# LPEDT_revA1_bikeit_MCU_IO.net
KiCad netlist of a schematic drawn in Altium Designer
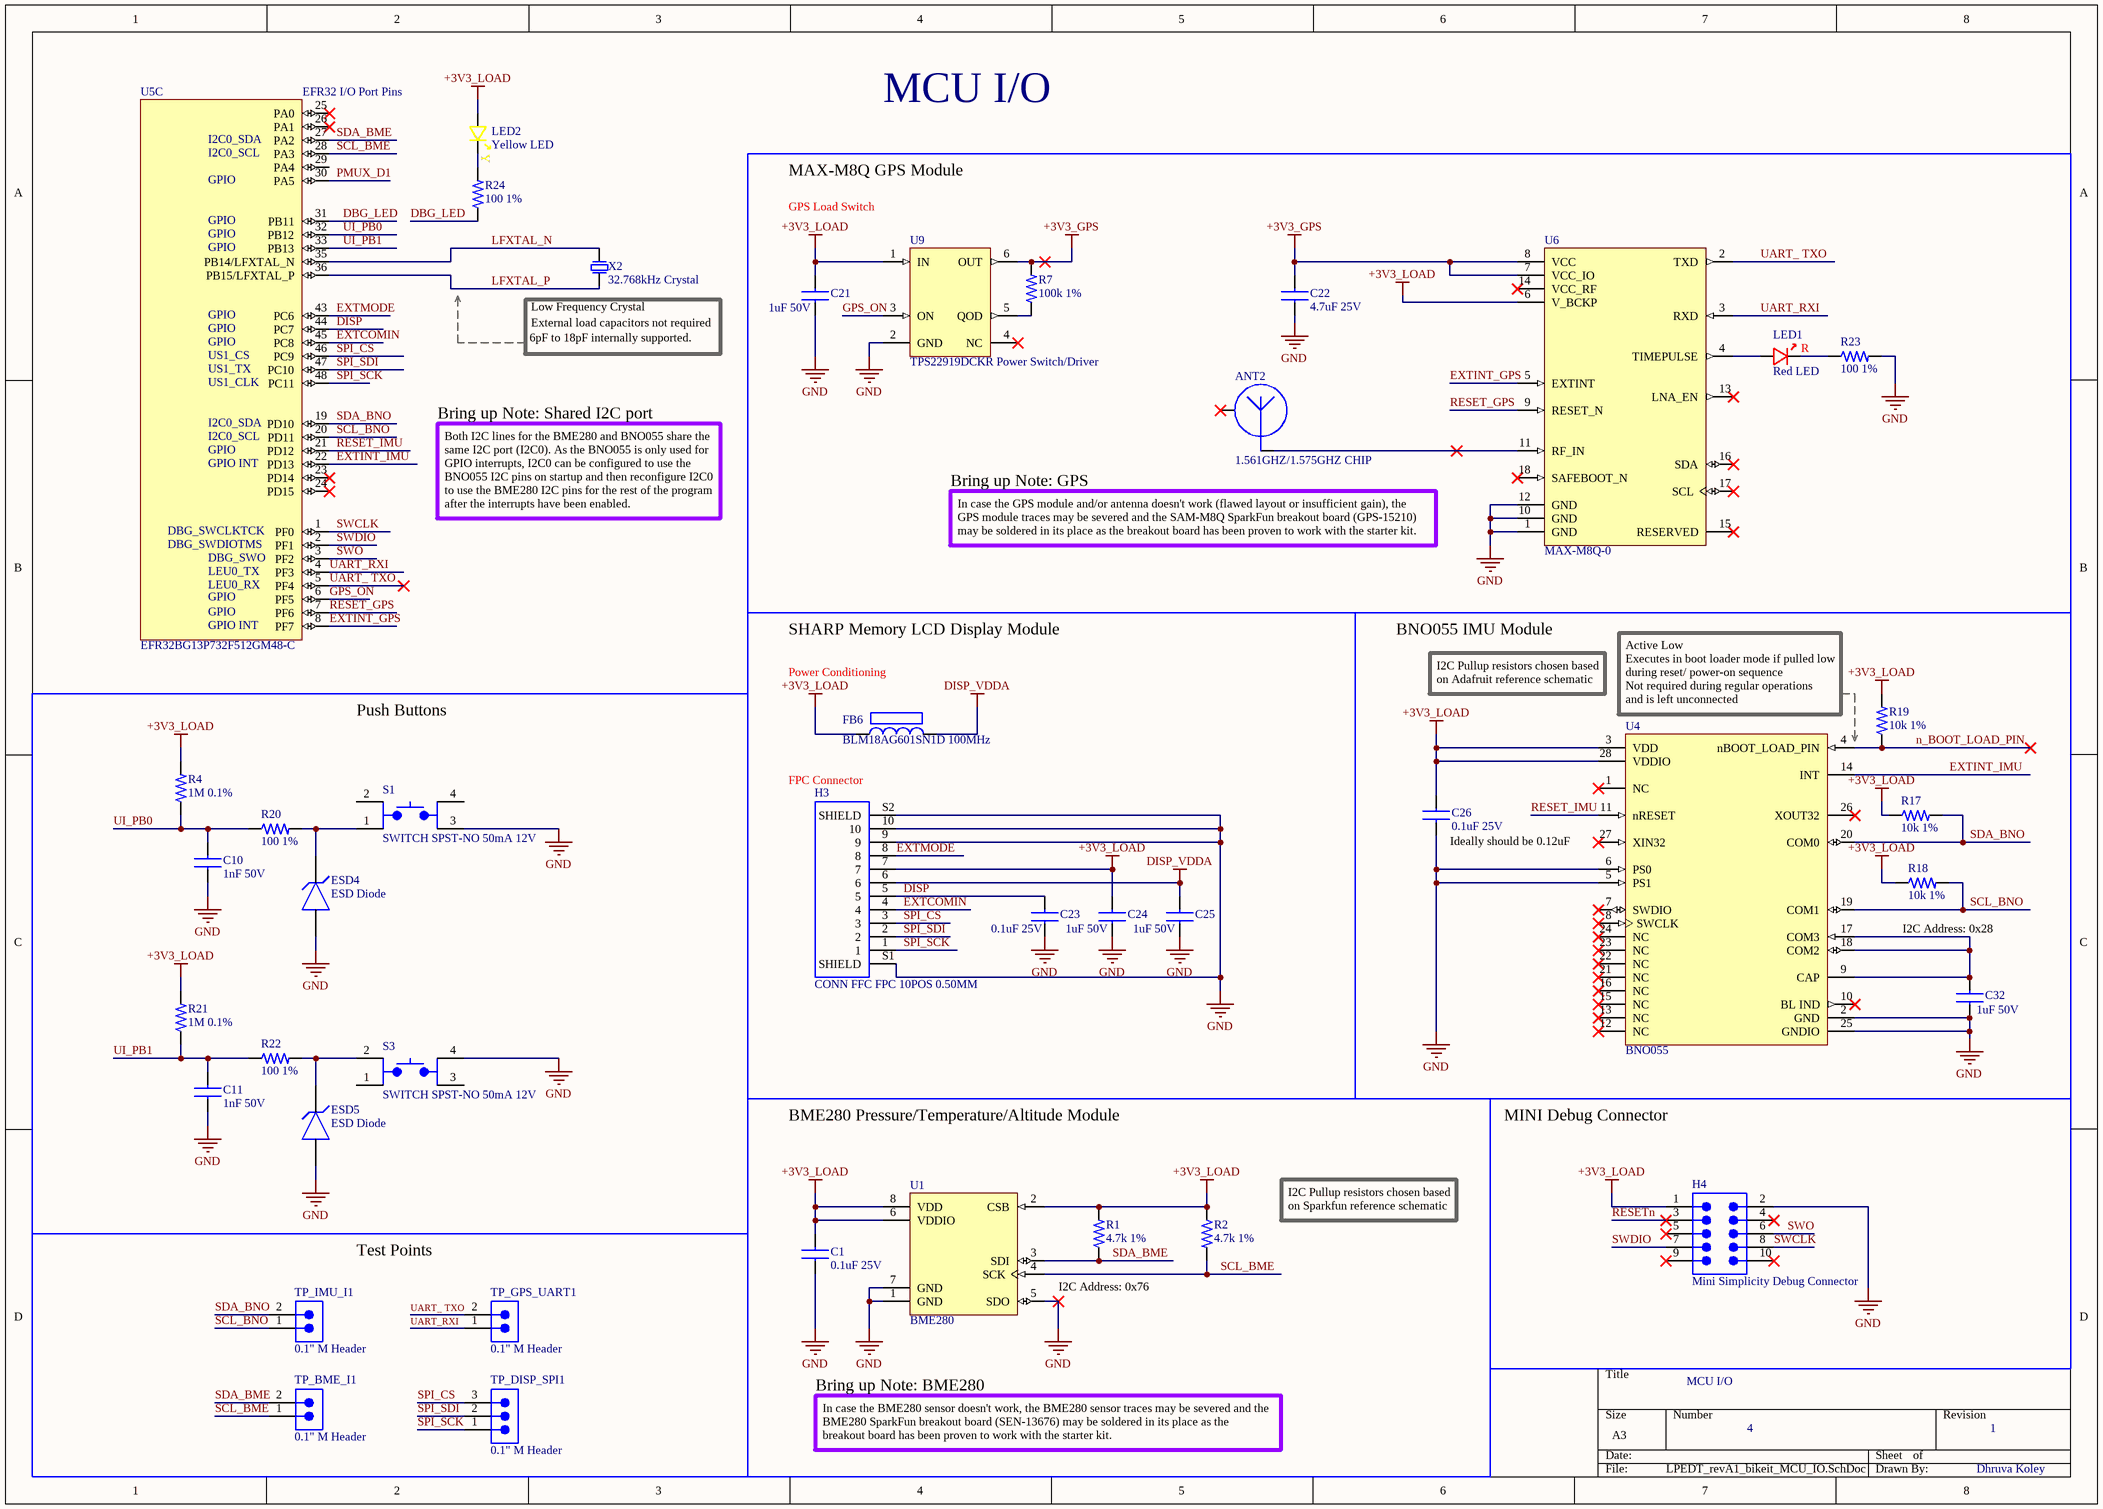
[diagram p0: LPEDT_revA1_bikeit_MCU_IO.SchDoc]

(export (version "E")
  (design (tool "Eeschema 10.0.6"))
  (components
    (comp (ref "ANT2")
      (value "1.561GHZ/1.575GHZ CHIP")
      (footprint "CHIP_ANTENNA")
      (description "RF ANT 1.561GHZ/1.575GHZ CHIP")
      (fields
        (field (name "MANUFACTURER") "Johanson")
        (field (name "MANUFACTURER PART NUMBER") "1575AT43A0040E")
      )
      (libsource (lib "LPEDT_revA1_bikeit_IL") (part "1575AT43A0040E"))
    )
    (comp (ref "C1")
      (value "0.1uF 25V")
      (footprint "CAP_0603_1.60mm*0.80mm")
      (description "CAP CER 0.1UF 25V X7R 0603")
      (fields
        (field (name "MANUFACTURER") "Murata")
        (field (name "MANUFACTURER PART NUMBER") "GCJ188R71E104KA12D")
      )
      (libsource (lib "LPEDT_revA1_bikeit") (part "GCJ188R71E104KA12D"))
    )
    (comp (ref "C10")
      (value "1nF 50V")
      (footprint "CAP_0603_1.60mm*0.80mm")
      (description "Cap Ceramic 0.001uF 50V X7R 10% Pad SMD 0603 125°C T/R")
      (fields
        (field (name "MANUFACTURER") "Samsung")
        (field (name "MANUFACTURER PART NUMBER") "CL10B102KB8NNNC")
      )
      (libsource (lib "LPEDT_revA1_bikeit_IL") (part "CL10B102KB8NNNC"))
    )
    (comp (ref "C11")
      (value "1nF 50V")
      (footprint "CAP_0603_1.60mm*0.80mm")
      (description "Cap Ceramic 0.001uF 50V X7R 10% Pad SMD 0603 125°C T/R")
      (fields
        (field (name "MANUFACTURER") "Samsung")
        (field (name "MANUFACTURER PART NUMBER") "CL10B102KB8NNNC")
      )
      (libsource (lib "LPEDT_revA1_bikeit_IL") (part "CL10B102KB8NNNC"))
    )
    (comp (ref "C21")
      (value "1uF 50V")
      (footprint "CAP_0603_1.60mm*0.80mm")
      (description "CAP, MLCC, AEC-Q200, X5R, 1uF, 50V, 0603")
      (fields
        (field (name "MANUFACTURER") "Murata")
        (field (name "MANUFACTURER PART NUMBER") "GRT188R61H105KE13D")
      )
      (libsource (lib "LPEDT_revA1_bikeit_IL") (part "GRT188R61H105KE13D"))
    )
    (comp (ref "C22")
      (value "4.7uF 25V")
      (footprint "CAP_0603_1.60mm*0.80mm")
      (description "Cap Ceramic 0603 4.7 uF 25 V ±10 % Tolerance X5R SMT Multilayer Ceramic Capacitor")
      (fields
        (field (name "MANUFACTURER") "Murata")
        (field (name "MANUFACTURER PART NUMBER") "GRM188R61E475KE11D")
      )
      (libsource (lib "LPEDT_revA1_bikeit_IL") (part "GRM188R61E475KE11D"))
    )
    (comp (ref "C23")
      (value "0.1uF 25V")
      (footprint "CAP_0603_1.60mm*0.80mm")
      (description "CAP CER 0.1UF 25V X7R 0603")
      (fields
        (field (name "MANUFACTURER") "Murata")
        (field (name "MANUFACTURER PART NUMBER") "GCJ188R71E104KA12D")
      )
      (libsource (lib "LPEDT_revA1_bikeit") (part "GCJ188R71E104KA12D"))
    )
    (comp (ref "C24")
      (value "1uF 50V")
      (footprint "CAP_0603_1.60mm*0.80mm")
      (description "CAP, MLCC, AEC-Q200, X5R, 1uF, 50V, 0603")
      (fields
        (field (name "MANUFACTURER") "Murata")
        (field (name "MANUFACTURER PART NUMBER") "GRT188R61H105KE13D")
      )
      (libsource (lib "LPEDT_revA1_bikeit_IL") (part "GRT188R61H105KE13D"))
    )
    (comp (ref "C25")
      (value "1uF 50V")
      (footprint "CAP_0603_1.60mm*0.80mm")
      (description "CAP, MLCC, AEC-Q200, X5R, 1uF, 50V, 0603")
      (fields
        (field (name "MANUFACTURER") "Murata")
        (field (name "MANUFACTURER PART NUMBER") "GRT188R61H105KE13D")
      )
      (libsource (lib "LPEDT_revA1_bikeit_IL") (part "GRT188R61H105KE13D"))
    )
    (comp (ref "C26")
      (value "0.1uF 25V")
      (footprint "CAP_0603_1.60mm*0.80mm")
      (description "CAP CER 0.1UF 25V X7R 0603")
      (fields
        (field (name "MANUFACTURER") "Murata")
        (field (name "MANUFACTURER PART NUMBER") "GCJ188R71E104KA12D")
      )
      (libsource (lib "LPEDT_revA1_bikeit") (part "GCJ188R71E104KA12D"))
    )
    (comp (ref "C32")
      (value "1uF 50V")
      (footprint "CAP_0603_1.60mm*0.80mm")
      (description "CAP, MLCC, AEC-Q200, X5R, 1uF, 50V, 0603")
      (fields
        (field (name "MANUFACTURER") "Murata")
        (field (name "MANUFACTURER PART NUMBER") "GRT188R61H105KE13D")
      )
      (libsource (lib "LPEDT_revA1_bikeit_IL") (part "GRT188R61H105KE13D"))
    )
    (comp (ref "ESD4")
      (value "ESD Diode")
      (footprint "ESD_SOD882")
      (description "ESD Suppressor Diode TVS Uni-Dir 5V Automotive 2-Pin SOD-882 T/R")
      (fields
        (field (name "MANUFACTURER") "Littelfuse")
        (field (name "MANUFACTURER PART NUMBER") "SP1003-01ETG")
      )
      (libsource (lib "LPEDT_revA1_bikeit_IL") (part "SP1003-01ETG"))
    )
    (comp (ref "ESD5")
      (value "ESD Diode")
      (footprint "ESD_SOD882")
      (description "ESD Suppressor Diode TVS Uni-Dir 5V Automotive 2-Pin SOD-882 T/R")
      (fields
        (field (name "MANUFACTURER") "Littelfuse")
        (field (name "MANUFACTURER PART NUMBER") "SP1003-01ETG")
      )
      (libsource (lib "LPEDT_revA1_bikeit_IL") (part "SP1003-01ETG"))
    )
    (comp (ref "FB6")
      (value "BLM18AG601SN1D 100MHz")
      (footprint "FB_Chip2PinSM127P600-8N")
      (description "Ferrite Bead, 0603 / 1608, 600 ohm, 500 mA, Série BLM18A, 0.38 ohm, ± 25%")
      (fields
        (field (name "MANUFACTURER") "Murata")
        (field (name "MANUFACTURER PART NUMBER") "BLM18AG601SN1D")
      )
      (libsource (lib "LPEDT_revA1_bikeit_IL") (part "BLM18AG601SN1D"))
    )
    (comp (ref "H3")
      (value "CONN FFC FPC 10POS 0.50MM")
      (footprint "FPC_AYF531035A")
      (description "10 Position 0.5 mm Solder Right Angle FFC / FPC SMD Socket")
      (fields
        (field (name "MANUFACTURER") "Panasonic")
        (field (name "MANUFACTURER PART NUMBER") "AYF531035A")
      )
      (libsource (lib "LPEDT_revA1_bikeit_IL") (part "AYF531035A"))
    )
    (comp (ref "H4")
      (value "Mini Simplicity Debug Connector")
      (footprint "FTSH-105-01-XXX-DV-K")
      (description "Conn Unshrouded Header HDR 10 POS 1.27mm Solder ST SMD Tube")
      (fields
        (field (name "MANUFACTURER") "Samtec")
        (field (name "MANUFACTURER PART NUMBER") "FTSH-105-01-LM-DV-K")
      )
      (libsource (lib "LPEDT_revA1_bikeit_IL") (part "FTSH-105-01-LM-DV-K"))
    )
    (comp (ref "LED1")
      (value "Red LED")
      (footprint "LED_0603_RED_WL-SMCW")
      (description "WURTH ELEKTRONIK - 150060RS75000 - LED, Red, 625 nm, 2 V, 30 mA, 250 mcd RoHS Compliant: Yes")
      (fields
        (field (name "MANUFACTURER") "Wurth Electronics")
        (field (name "MANUFACTURER PART NUMBER") "150060RS75000")
      )
      (libsource (lib "LPEDT_revA1_bikeit_IL") (part "150060RS75000"))
    )
    (comp (ref "LED2")
      (value "Yellow LED")
      (footprint "LED_0603_YLW_WL-SMCW")
      (description "WURTH ELEKTRONIK - 150060YS75000 - LED, Yellow, SMD, 0603, 30 mA, 2 V, 590 nm")
      (fields
        (field (name "MANUFACTURER") "Wurth Electronics")
        (field (name "MANUFACTURER PART NUMBER") "150060YS75000")
      )
      (libsource (lib "LPEDT_revA1_bikeit_IL") (part "150060YS75000"))
    )
    (comp (ref "R1")
      (value "4.7k 1%")
      (footprint "RES_0603_1608X06")
      (description "RES SMD 4.7k  1% 0603")
      (fields
        (field (name "MANUFACTURER") "Yageo")
        (field (name "MANUFACTURER PART NUMBER") "RC0603FR-074K7L")
      )
      (libsource (lib "LPEDT_revA1_bikeit_IL") (part "RC0603FR-074K7L"))
    )
    (comp (ref "R2")
      (value "4.7k 1%")
      (footprint "RES_0603_1608X06")
      (description "RES SMD 4.7k  1% 0603")
      (fields
        (field (name "MANUFACTURER") "Yageo")
        (field (name "MANUFACTURER PART NUMBER") "RC0603FR-074K7L")
      )
      (libsource (lib "LPEDT_revA1_bikeit_IL") (part "RC0603FR-074K7L"))
    )
    (comp (ref "R4")
      (value "1M 0.1%")
      (footprint "RES_0603_1608X06")
      (description "Res Thin Film 0603 1M Ohm 0.1% 1/16W ±25ppm/°C Molded SMD SMD Paper T/R")
      (fields
        (field (name "MANUFACTURER") "TE Connectivity Neohm")
        (field (name "MANUFACTURER PART NUMBER") "CPF0603B1M0E1")
      )
      (libsource (lib "LPEDT_revA1_bikeit_IL") (part "CPF0603B1M0E1"))
    )
    (comp (ref "R7")
      (value "100k 1%")
      (footprint "RES_0603_1608X06")
      (description "RES SMD 100k  1% 1/10W 0603")
      (fields
        (field (name "MANUFACTURER") "Yageo")
        (field (name "MANUFACTURER PART NUMBER") "RC0603FR-07100KL")
      )
      (libsource (lib "LPEDT_revA1_bikeit_IL") (part "RC0603FR-07100KL"))
    )
    (comp (ref "R17")
      (value "10k 1%")
      (footprint "RES_0603_1608X06")
      (description "RES SMD 10k 1% 1/10W 0603")
      (fields
        (field (name "MANUFACTURER") "Yageo")
        (field (name "MANUFACTURER PART NUMBER") "RC0603FR-0710KL")
      )
      (libsource (lib "LPEDT_revA1_bikeit_IL") (part "RC0603FR-0710KL"))
    )
    (comp (ref "R18")
      (value "10k 1%")
      (footprint "RES_0603_1608X06")
      (description "RES SMD 10k 1% 1/10W 0603")
      (fields
        (field (name "MANUFACTURER") "Yageo")
        (field (name "MANUFACTURER PART NUMBER") "RC0603FR-0710KL")
      )
      (libsource (lib "LPEDT_revA1_bikeit_IL") (part "RC0603FR-0710KL"))
    )
    (comp (ref "R19")
      (value "10k 1%")
      (footprint "RES_0603_1608X06")
      (description "RES SMD 10k 1% 1/10W 0603")
      (fields
        (field (name "MANUFACTURER") "Yageo")
        (field (name "MANUFACTURER PART NUMBER") "RC0603FR-0710KL")
      )
      (libsource (lib "LPEDT_revA1_bikeit_IL") (part "RC0603FR-0710KL"))
    )
    (comp (ref "R20")
      (value "100 1%")
      (footprint "RES_0603_1608X06")
      (description "RES SMD 100 1%")
      (fields
        (field (name "MANUFACTURER") "Stackpole Electronics")
        (field (name "MANUFACTURER PART NUMBER") "RMCF0603FT100R")
      )
      (libsource (lib "LPEDT_revA1_bikeit_IL") (part "RMCF0603FT100R"))
    )
    (comp (ref "R21")
      (value "1M 0.1%")
      (footprint "RES_0603_1608X06")
      (description "Res Thin Film 0603 1M Ohm 0.1% 1/16W ±25ppm/°C Molded SMD SMD Paper T/R")
      (fields
        (field (name "MANUFACTURER") "TE Connectivity Neohm")
        (field (name "MANUFACTURER PART NUMBER") "CPF0603B1M0E1")
      )
      (libsource (lib "LPEDT_revA1_bikeit_IL") (part "CPF0603B1M0E1"))
    )
    (comp (ref "R22")
      (value "100 1%")
      (footprint "RES_0603_1608X06")
      (description "RES SMD 100 1%")
      (fields
        (field (name "MANUFACTURER") "Stackpole Electronics")
        (field (name "MANUFACTURER PART NUMBER") "RMCF0603FT100R")
      )
      (libsource (lib "LPEDT_revA1_bikeit_IL") (part "RMCF0603FT100R"))
    )
    (comp (ref "R23")
      (value "100 1%")
      (footprint "RES_0603_1608X06")
      (description "RES SMD 100 1%")
      (fields
        (field (name "MANUFACTURER") "Stackpole Electronics")
        (field (name "MANUFACTURER PART NUMBER") "RMCF0603FT100R")
      )
      (libsource (lib "LPEDT_revA1_bikeit_IL") (part "RMCF0603FT100R"))
    )
    (comp (ref "R24")
      (value "100 1%")
      (footprint "RES_0603_1608X06")
      (description "RES SMD 100 1%")
      (fields
        (field (name "MANUFACTURER") "Stackpole Electronics")
        (field (name "MANUFACTURER PART NUMBER") "RMCF0603FT100R")
      )
      (libsource (lib "LPEDT_revA1_bikeit_IL") (part "RMCF0603FT100R"))
    )
    (comp (ref "S1")
      (value "SWITCH SPST-NO 50mA 12V")
      (footprint "SW_TL3305AF260QG")
      (description "SWITCH TACTILE SPST-NO 50MA 12V")
      (fields
        (field (name "MANUFACTURER") "E-Switch")
        (field (name "MANUFACTURER PART NUMBER") "TL3305AF260QG")
      )
      (libsource (lib "LPEDT_revA1_bikeit_IL") (part "TL3305AF260QG"))
    )
    (comp (ref "S3")
      (value "SWITCH SPST-NO 50mA 12V")
      (footprint "SW_TL3305AF260QG")
      (description "SWITCH TACTILE SPST-NO 50MA 12V")
      (fields
        (field (name "MANUFACTURER") "E-Switch")
        (field (name "MANUFACTURER PART NUMBER") "TL3305AF260QG")
      )
      (libsource (lib "LPEDT_revA1_bikeit_IL") (part "TL3305AF260QG"))
    )
    (comp (ref "TP_BME_I1")
      (value "0.1\" M Header")
      (footprint "2-PIN_MALE_NO 3D")
      (description "CONN HEADER VERT 2POS 2.54MM")
      (fields
        (field (name "MANUFACTURER") "Sullins")
        (field (name "MANUFACTURER PART NUMBER") "PRPC002SAAN-RC")
      )
      (libsource (lib "LPEDT_revA1_bikeit_IL") (part "PRPC002SAAN-RC_1"))
    )
    (comp (ref "TP_DISP_SPI1")
      (value "0.1\" M Header")
      (footprint "3-PIN_MALE_NO 3D")
      (description "CONN HEADER VERT 3POS 2.54MM")
      (fields
        (field (name "MANUFACTURER") "Sullins")
        (field (name "MANUFACTURER PART NUMBER") "PRPC003SAAN-RC")
      )
      (libsource (lib "LPEDT_revA1_bikeit_IL") (part "PRPC003SAAN-RC_1"))
    )
    (comp (ref "TP_GPS_UART1")
      (value "0.1\" M Header")
      (footprint "2-PIN_MALE_NO 3D")
      (description "CONN HEADER VERT 2POS 2.54MM")
      (fields
        (field (name "MANUFACTURER") "Sullins")
        (field (name "MANUFACTURER PART NUMBER") "PRPC002SAAN-RC")
      )
      (libsource (lib "LPEDT_revA1_bikeit_IL") (part "PRPC002SAAN-RC_1"))
    )
    (comp (ref "TP_IMU_I1")
      (value "0.1\" M Header")
      (footprint "2-PIN_MALE_NO 3D")
      (description "CONN HEADER VERT 2POS 2.54MM")
      (fields
        (field (name "MANUFACTURER") "Sullins")
        (field (name "MANUFACTURER PART NUMBER") "PRPC002SAAN-RC")
      )
      (libsource (lib "LPEDT_revA1_bikeit_IL") (part "PRPC002SAAN-RC_1"))
    )
    (comp (ref "U1")
      (value "BME280")
      (footprint "BME280_PSON65P250X250X100-8N")
      (description "Humidity Temperature Sensor 0 ~ 100% RH I²C, SPI ±3% 1s Surface Mount")
      (fields (field (name "MF") "Bosch"))
      (libsource (lib "LPEDT_revA1_bikeit_IL") (part "BME280"))
    )
    (comp (ref "U4")
      (value "BNO055")
      (footprint "BNO055-MFG")
      (description "IMU ACCEL/GYRO/MAG I2C 28LGA\r\nCMP-2000-05075-4")
      (libsource (lib "LPEDT_revA1_bikeit_IL") (part "BNO055"))
    )
    (comp (ref "U5")
      (value "EFR32BG13P732F512GM48-C")
      (footprint "MCU_QFN50P700X700X90_HS-49N")
      (description "BLUE GECKO QFN48 2.4 GHZ 512KB 6")
      (fields (field (name "MANUFACTURER") "Silicon Labs"))
      (libsource (lib "LPEDT_revA1_bikeit_IL") (part "EFR32BG13P732F512GM48-C"))
    )
    (comp (ref "U6")
      (value "MAX-M8Q-0")
      (footprint "XCVR_MAX-M8C-0-10")
      (description "MAX-M8 RF Receiver BeiDou, Galileo, GLONASS, GNSS, GPS 1.575GHz -167dBm")
      (fields (field (name "MF") "U-Blox America"))
      (libsource (lib "LPEDT_revA1_bikeit") (part "MAX-M8Q-0"))
    )
    (comp (ref "U9")
      (value "TPS22919DCKR Power Switch/Driver")
      (footprint "LS_SOT65P210X110-6N")
      (description "5.5-V, 1.5-A, 90-mΩ load switch with adj. output discharge 6-SC70 -40 to 105")
      (fields
        (field (name "MANUFACTURER") "Texas Instruments")
        (field (name "MANUFACTURER PART NUMBER") "TPS22919DCKR")
      )
      (libsource (lib "LPEDT_revA1_bikeit_IL") (part "TPS22919DCKR"))
    )
    (comp (ref "X2")
      (value "32.768kHz Crystal")
      (footprint "SMD_2 Crystal")
      (description "32.768kHz ±20ppm Crystal 12.5pF 70 kOhms 2-SMD, No Lead")
      (fields
        (field (name "MANUFACTURER") "Micro Crystal")
        (field (name "MANUFACTURER PART NUMBER") "CM8V-T1A-32.768KHZ-12.5PF-20PPM-TB-QA")
      )
      (libsource (lib "LPEDT_revA1_bikeit_IL") (part "CM8V-T1A-32.768KHZ-12.5PF-20PPM-TB-QA"))
    )
  )
  (nets
    (net (code "1") (name "+3V3_GPS") (class "Default")
      (node (ref "C22") (pin "1") (pinfunction "1_1") (pintype "passive"))
      (node (ref "R7") (pin "2") (pinfunction "2_2") (pintype "passive"))
      (node (ref "U6") (pin "7") (pinfunction "VCC_IO_7") (pintype "power_in"))
      (node (ref "U6") (pin "8") (pinfunction "VCC_8") (pintype "power_in"))
      (node (ref "U9") (pin "6") (pinfunction "OUT_6") (pintype "output"))
    )
    (net (code "2") (name "+3V3_LOAD") (class "Default")
      (node (ref "C1") (pin "1") (pinfunction "1_1") (pintype "passive"))
      (node (ref "C21") (pin "1") (pinfunction "1_1") (pintype "passive"))
      (node (ref "C24") (pin "1") (pinfunction "1_1") (pintype "passive"))
      (node (ref "C26") (pin "1") (pinfunction "1_1") (pintype "passive"))
      (node (ref "FB6") (pin "1") (pinfunction "1_1") (pintype "passive"))
      (node (ref "H3") (pin "7") (pinfunction "7_7") (pintype "passive"))
      (node (ref "H4") (pin "1") (pinfunction "1_1") (pintype "passive"))
      (node (ref "LED2") (pin "A") (pinfunction "A_A") (pintype "passive"))
      (node (ref "R1") (pin "2") (pinfunction "2_2") (pintype "passive"))
      (node (ref "R17") (pin "1") (pinfunction "1_1") (pintype "passive"))
      (node (ref "R18") (pin "1") (pinfunction "1_1") (pintype "passive"))
      (node (ref "R19") (pin "2") (pinfunction "2_2") (pintype "passive"))
      (node (ref "R2") (pin "1") (pinfunction "1_1") (pintype "passive"))
      (node (ref "R21") (pin "2") (pinfunction "2_2") (pintype "passive"))
      (node (ref "R4") (pin "2") (pinfunction "2_2") (pintype "passive"))
      (node (ref "U1") (pin "2") (pinfunction "CSB_2") (pintype "input"))
      (node (ref "U1") (pin "6") (pinfunction "VDDIO_6") (pintype "power_in"))
      (node (ref "U1") (pin "8") (pinfunction "VDD_8") (pintype "power_in"))
      (node (ref "U4") (pin "28") (pinfunction "VDDIO_28") (pintype "power_in"))
      (node (ref "U4") (pin "3") (pinfunction "VDD_3") (pintype "power_in"))
      (node (ref "U6") (pin "6") (pinfunction "V_BCKP_6") (pintype "power_in"))
      (node (ref "U9") (pin "1") (pinfunction "IN_1") (pintype "input"))
    )
    (net (code "3") (name "/DBG_LED") (class "Default")
      (node (ref "R24") (pin "1") (pinfunction "1_1") (pintype "passive"))
      (node (ref "U5") (pin "31") (pinfunction "PB11_31") (pintype "bidirectional"))
    )
    (net (code "4") (name "/DISP") (class "Default")
      (node (ref "C23") (pin "1") (pinfunction "1_1") (pintype "passive"))
      (node (ref "H3") (pin "5") (pinfunction "5_5") (pintype "passive"))
      (node (ref "U5") (pin "44") (pinfunction "PC7_44") (pintype "bidirectional"))
    )
    (net (code "5") (name "/EXTCOMIN") (class "Default")
      (node (ref "H3") (pin "4") (pinfunction "4_4") (pintype "passive"))
      (node (ref "U5") (pin "45") (pinfunction "PC8_45") (pintype "bidirectional"))
    )
    (net (code "6") (name "/EXTINT_GPS") (class "Default")
      (node (ref "U5") (pin "8") (pinfunction "PF7_8") (pintype "bidirectional"))
      (node (ref "U6") (pin "5") (pinfunction "EXTINT_5") (pintype "input"))
    )
    (net (code "7") (name "/EXTINT_IMU") (class "Default")
      (node (ref "U4") (pin "14") (pinfunction "INT_14") (pintype "passive"))
      (node (ref "U5") (pin "22") (pinfunction "PD13_22") (pintype "bidirectional"))
    )
    (net (code "8") (name "/EXTMODE") (class "Default")
      (node (ref "H3") (pin "8") (pinfunction "8_8") (pintype "passive"))
      (node (ref "U5") (pin "43") (pinfunction "PC6_43") (pintype "bidirectional"))
    )
    (net (code "9") (name "/GPS_ON") (class "Default")
      (node (ref "U5") (pin "6") (pinfunction "PF5_6") (pintype "bidirectional"))
      (node (ref "U9") (pin "3") (pinfunction "ON_3") (pintype "input"))
    )
    (net (code "10") (name "/LFXTAL_N") (class "Default")
      (node (ref "U5") (pin "35") (pinfunction "PB14/LFXTAL_N_35") (pintype "bidirectional"))
      (node (ref "X2") (pin "2") (pinfunction "2_2") (pintype "passive"))
    )
    (net (code "11") (name "/LFXTAL_P") (class "Default")
      (node (ref "U5") (pin "36") (pinfunction "PB15/LFXTAL_P_36") (pintype "bidirectional"))
      (node (ref "X2") (pin "1") (pinfunction "1_1") (pintype "passive"))
    )
    (net (code "12") (name "/PMUX_D1") (class "Default")
      (node (ref "U5") (pin "30") (pinfunction "PA5_30") (pintype "bidirectional"))
    )
    (net (code "13") (name "/RESET_GPS") (class "Default")
      (node (ref "U5") (pin "7") (pinfunction "PF6_7") (pintype "bidirectional"))
      (node (ref "U6") (pin "9") (pinfunction "RESET_N_9") (pintype "input"))
    )
    (net (code "14") (name "/RESET_IMU") (class "Default")
      (node (ref "U4") (pin "11") (pinfunction "nRESET_11") (pintype "input"))
      (node (ref "U5") (pin "21") (pinfunction "PD12_21") (pintype "bidirectional"))
    )
    (net (code "15") (name "/RESETn") (class "Default")
      (node (ref "H4") (pin "3") (pinfunction "3_3") (pintype "passive+no_connect"))
    )
    (net (code "16") (name "/SCL_BME") (class "Default")
      (node (ref "R2") (pin "2") (pinfunction "2_2") (pintype "passive"))
      (node (ref "TP_BME_I1") (pin "1") (pinfunction "1_1") (pintype "passive"))
      (node (ref "U1") (pin "4") (pinfunction "SCK_4") (pintype "input"))
      (node (ref "U5") (pin "28") (pinfunction "PA3_28") (pintype "bidirectional"))
    )
    (net (code "17") (name "/SCL_BNO") (class "Default")
      (node (ref "R18") (pin "2") (pinfunction "2_2") (pintype "passive"))
      (node (ref "TP_IMU_I1") (pin "1") (pinfunction "1_1") (pintype "passive"))
      (node (ref "U4") (pin "19") (pinfunction "COM1_19") (pintype "bidirectional"))
      (node (ref "U5") (pin "20") (pinfunction "PD11_20") (pintype "bidirectional"))
    )
    (net (code "18") (name "/SDA_BME") (class "Default")
      (node (ref "R1") (pin "1") (pinfunction "1_1") (pintype "passive"))
      (node (ref "TP_BME_I1") (pin "2") (pinfunction "2_2") (pintype "passive"))
      (node (ref "U1") (pin "3") (pinfunction "SDI_3") (pintype "bidirectional"))
      (node (ref "U5") (pin "27") (pinfunction "PA2_27") (pintype "bidirectional"))
    )
    (net (code "19") (name "/SDA_BNO") (class "Default")
      (node (ref "R17") (pin "2") (pinfunction "2_2") (pintype "passive"))
      (node (ref "TP_IMU_I1") (pin "2") (pinfunction "2_2") (pintype "passive"))
      (node (ref "U4") (pin "20") (pinfunction "COM0_20") (pintype "bidirectional"))
      (node (ref "U5") (pin "19") (pinfunction "PD10_19") (pintype "bidirectional"))
    )
    (net (code "20") (name "/SPI_CS") (class "Default")
      (node (ref "H3") (pin "3") (pinfunction "3_3") (pintype "passive"))
      (node (ref "TP_DISP_SPI1") (pin "3") (pinfunction "3_3") (pintype "passive"))
      (node (ref "U5") (pin "46") (pinfunction "PC9_46") (pintype "bidirectional"))
    )
    (net (code "21") (name "/SPI_SCK") (class "Default")
      (node (ref "H3") (pin "1") (pinfunction "1_1") (pintype "passive"))
      (node (ref "TP_DISP_SPI1") (pin "1") (pinfunction "1_1") (pintype "passive"))
      (node (ref "U5") (pin "48") (pinfunction "PC11_48") (pintype "bidirectional"))
    )
    (net (code "22") (name "/SPI_SDI") (class "Default")
      (node (ref "H3") (pin "2") (pinfunction "2_2") (pintype "passive"))
      (node (ref "TP_DISP_SPI1") (pin "2") (pinfunction "2_2") (pintype "passive"))
      (node (ref "U5") (pin "47") (pinfunction "PC10_47") (pintype "bidirectional"))
    )
    (net (code "23") (name "/SWCLK") (class "Default")
      (node (ref "H4") (pin "8") (pinfunction "8_8") (pintype "passive"))
      (node (ref "U5") (pin "1") (pinfunction "PF0_1") (pintype "bidirectional"))
    )
    (net (code "24") (name "/SWDIO") (class "Default")
      (node (ref "H4") (pin "7") (pinfunction "7_7") (pintype "passive"))
      (node (ref "U5") (pin "2") (pinfunction "PF1_2") (pintype "bidirectional"))
    )
    (net (code "25") (name "/SWO") (class "Default")
      (node (ref "H4") (pin "6") (pinfunction "6_6") (pintype "passive"))
      (node (ref "U5") (pin "3") (pinfunction "PF2_3") (pintype "bidirectional"))
    )
    (net (code "26") (name "/UART_ TXO") (class "Default")
      (node (ref "TP_GPS_UART1") (pin "2") (pinfunction "2_2") (pintype "passive"))
      (node (ref "U5") (pin "5") (pinfunction "PF4_5") (pintype "bidirectional"))
      (node (ref "U6") (pin "2") (pinfunction "TXD_2") (pintype "output"))
    )
    (net (code "27") (name "/UART_RXI") (class "Default")
      (node (ref "TP_GPS_UART1") (pin "1") (pinfunction "1_1") (pintype "passive"))
      (node (ref "U5") (pin "4") (pinfunction "PF3_4") (pintype "bidirectional"))
      (node (ref "U6") (pin "3") (pinfunction "RXD_3") (pintype "input"))
    )
    (net (code "28") (name "/UI_PB0") (class "Default")
      (node (ref "C10") (pin "1") (pinfunction "1_1") (pintype "passive"))
      (node (ref "R20") (pin "1") (pinfunction "1_1") (pintype "passive"))
      (node (ref "R4") (pin "1") (pinfunction "1_1") (pintype "passive"))
      (node (ref "U5") (pin "32") (pinfunction "PB12_32") (pintype "bidirectional"))
    )
    (net (code "29") (name "/UI_PB1") (class "Default")
      (node (ref "C11") (pin "1") (pinfunction "1_1") (pintype "passive"))
      (node (ref "R21") (pin "1") (pinfunction "1_1") (pintype "passive"))
      (node (ref "R22") (pin "1") (pinfunction "1_1") (pintype "passive"))
      (node (ref "U5") (pin "33") (pinfunction "PB13_33") (pintype "bidirectional"))
    )
    (net (code "30") (name "/n_BOOT_LOAD_PIN") (class "Default")
      (node (ref "R19") (pin "1") (pinfunction "1_1") (pintype "passive"))
      (node (ref "U4") (pin "4") (pinfunction "nBOOT_LOAD_PIN_4") (pintype "input"))
    )
    (net (code "31") (name "DISP_VDDA") (class "Default")
      (node (ref "C25") (pin "1") (pinfunction "1_1") (pintype "passive"))
      (node (ref "FB6") (pin "2") (pinfunction "2_2") (pintype "passive"))
      (node (ref "H3") (pin "6") (pinfunction "6_6") (pintype "passive"))
    )
    (net (code "32") (name "GND") (class "Default")
      (node (ref "C1") (pin "2") (pinfunction "2_2") (pintype "passive"))
      (node (ref "C10") (pin "2") (pinfunction "2_2") (pintype "passive"))
      (node (ref "C11") (pin "2") (pinfunction "2_2") (pintype "passive"))
      (node (ref "C21") (pin "2") (pinfunction "2_2") (pintype "passive"))
      (node (ref "C22") (pin "2") (pinfunction "2_2") (pintype "passive"))
      (node (ref "C23") (pin "2") (pinfunction "2_2") (pintype "passive"))
      (node (ref "C24") (pin "2") (pinfunction "2_2") (pintype "passive"))
      (node (ref "C25") (pin "2") (pinfunction "2_2") (pintype "passive"))
      (node (ref "C26") (pin "2") (pinfunction "2_2") (pintype "passive"))
      (node (ref "C32") (pin "2") (pinfunction "2_2") (pintype "passive"))
      (node (ref "ESD4") (pin "2") (pinfunction "2_2") (pintype "passive"))
      (node (ref "ESD5") (pin "2") (pinfunction "2_2") (pintype "passive"))
      (node (ref "H3") (pin "10") (pinfunction "10_10") (pintype "passive"))
      (node (ref "H3") (pin "9") (pinfunction "9_9") (pintype "passive"))
      (node (ref "H3") (pin "S1") (pinfunction "SHIELD_S1") (pintype "passive"))
      (node (ref "H3") (pin "S2") (pinfunction "SHIELD_S2") (pintype "passive"))
      (node (ref "H4") (pin "2") (pinfunction "2_2") (pintype "passive"))
      (node (ref "R23") (pin "2") (pinfunction "2_2") (pintype "passive"))
      (node (ref "S1") (pin "3") (pinfunction "3_3") (pintype "passive"))
      (node (ref "S3") (pin "4") (pinfunction "4_4") (pintype "passive"))
      (node (ref "U1") (pin "1") (pinfunction "GND_1") (pintype "passive"))
      (node (ref "U1") (pin "5") (pinfunction "SDO_5") (pintype "bidirectional"))
      (node (ref "U1") (pin "7") (pinfunction "GND_7") (pintype "passive"))
      (node (ref "U4") (pin "2") (pinfunction "GND_2") (pintype "power_in"))
      (node (ref "U4") (pin "25") (pinfunction "GNDIO_25") (pintype "power_in"))
      (node (ref "U4") (pin "5") (pinfunction "PS1_5") (pintype "input"))
      (node (ref "U4") (pin "6") (pinfunction "PS0_6") (pintype "input"))
      (node (ref "U6") (pin "1") (pinfunction "GND_1") (pintype "passive"))
      (node (ref "U6") (pin "10") (pinfunction "GND_10") (pintype "passive"))
      (node (ref "U6") (pin "12") (pinfunction "GND_12") (pintype "passive"))
      (node (ref "U9") (pin "2") (pinfunction "GND_2") (pintype "passive"))
    )
    (net (code "33") (name "Net-(ANT2-FEED)") (class "Default")
      (node (ref "ANT2") (pin "1") (pinfunction "FEED_1") (pintype "passive"))
      (node (ref "U6") (pin "11") (pinfunction "RF_IN_11") (pintype "input"))
    )
    (net (code "34") (name "Net-(ESD4-Pad1)") (class "Default")
      (node (ref "ESD4") (pin "1") (pinfunction "1_1") (pintype "passive"))
      (node (ref "R20") (pin "2") (pinfunction "2_2") (pintype "passive"))
      (node (ref "S1") (pin "1") (pinfunction "1_1") (pintype "passive"))
    )
    (net (code "35") (name "Net-(ESD5-Pad1)") (class "Default")
      (node (ref "ESD5") (pin "1") (pinfunction "1_1") (pintype "passive"))
      (node (ref "R22") (pin "2") (pinfunction "2_2") (pintype "passive"))
      (node (ref "S3") (pin "2") (pinfunction "2_2") (pintype "passive"))
    )
    (net (code "36") (name "Net-(LED1-PadC)") (class "Default")
      (node (ref "LED1") (pin "C") (pinfunction "C_C") (pintype "passive"))
      (node (ref "R23") (pin "1") (pinfunction "1_1") (pintype "passive"))
    )
    (net (code "37") (name "Net-(LED2-PadC)") (class "Default")
      (node (ref "LED2") (pin "C") (pinfunction "C_C") (pintype "passive"))
      (node (ref "R24") (pin "2") (pinfunction "2_2") (pintype "passive"))
    )
    (net (code "38") (name "Net-(U4-CAP)") (class "Default")
      (node (ref "C32") (pin "1") (pinfunction "1_1") (pintype "passive"))
      (node (ref "U4") (pin "17") (pinfunction "COM3_17") (pintype "input"))
      (node (ref "U4") (pin "18") (pinfunction "COM2_18") (pintype "bidirectional"))
      (node (ref "U4") (pin "9") (pinfunction "CAP_9") (pintype "passive"))
    )
    (net (code "39") (name "Net-(U6-TIMEPULSE)") (class "Default")
      (node (ref "LED1") (pin "A") (pinfunction "A_A") (pintype "passive"))
      (node (ref "U6") (pin "4") (pinfunction "TIMEPULSE_4") (pintype "output"))
    )
    (net (code "40") (name "Net-(U9-QOD)") (class "Default")
      (node (ref "R7") (pin "1") (pinfunction "1_1") (pintype "passive"))
      (node (ref "U9") (pin "5") (pinfunction "QOD_5") (pintype "output"))
    )
    (net (code "41") (name "unconnected-(ANT2-NC-Pad2)") (class "Default")
      (node (ref "ANT2") (pin "2") (pinfunction "NC_2") (pintype "passive+no_connect"))
    )
    (net (code "42") (name "unconnected-(H4-Pad4)") (class "Default")
      (node (ref "H4") (pin "4") (pinfunction "4_4") (pintype "passive+no_connect"))
    )
    (net (code "43") (name "unconnected-(H4-Pad5)") (class "Default")
      (node (ref "H4") (pin "5") (pinfunction "5_5") (pintype "passive+no_connect"))
    )
    (net (code "44") (name "unconnected-(H4-Pad9)") (class "Default")
      (node (ref "H4") (pin "9") (pinfunction "9_9") (pintype "passive+no_connect"))
    )
    (net (code "45") (name "unconnected-(H4-Pad10)") (class "Default")
      (node (ref "H4") (pin "10") (pinfunction "10_10") (pintype "passive+no_connect"))
    )
    (net (code "46") (name "unconnected-(S1-Pad2)") (class "Default")
      (node (ref "S1") (pin "2") (pinfunction "2_2") (pintype "passive"))
    )
    (net (code "47") (name "unconnected-(S1-Pad4)") (class "Default")
      (node (ref "S1") (pin "4") (pinfunction "4_4") (pintype "passive"))
    )
    (net (code "48") (name "unconnected-(S3-Pad1)") (class "Default")
      (node (ref "S3") (pin "1") (pinfunction "1_1") (pintype "passive"))
    )
    (net (code "49") (name "unconnected-(S3-Pad3)") (class "Default")
      (node (ref "S3") (pin "3") (pinfunction "3_3") (pintype "passive"))
    )
    (net (code "50") (name "unconnected-(U4-BL_IND-Pad10)") (class "Default")
      (node (ref "U4") (pin "10") (pinfunction "BL_IND_10") (pintype "output+no_connect"))
    )
    (net (code "51") (name "unconnected-(U4-NC-Pad1)") (class "Default")
      (node (ref "U4") (pin "1") (pinfunction "NC_1") (pintype "passive+no_connect"))
    )
    (net (code "52") (name "unconnected-(U4-NC-Pad12)") (class "Default")
      (node (ref "U4") (pin "12") (pinfunction "NC_12") (pintype "passive+no_connect"))
    )
    (net (code "53") (name "unconnected-(U4-NC-Pad13)") (class "Default")
      (node (ref "U4") (pin "13") (pinfunction "NC_13") (pintype "passive+no_connect"))
    )
    (net (code "54") (name "unconnected-(U4-NC-Pad15)") (class "Default")
      (node (ref "U4") (pin "15") (pinfunction "NC_15") (pintype "passive+no_connect"))
    )
    (net (code "55") (name "unconnected-(U4-NC-Pad16)") (class "Default")
      (node (ref "U4") (pin "16") (pinfunction "NC_16") (pintype "passive+no_connect"))
    )
    (net (code "56") (name "unconnected-(U4-NC-Pad21)") (class "Default")
      (node (ref "U4") (pin "21") (pinfunction "NC_21") (pintype "passive+no_connect"))
    )
    (net (code "57") (name "unconnected-(U4-NC-Pad22)") (class "Default")
      (node (ref "U4") (pin "22") (pinfunction "NC_22") (pintype "passive+no_connect"))
    )
    (net (code "58") (name "unconnected-(U4-NC-Pad23)") (class "Default")
      (node (ref "U4") (pin "23") (pinfunction "NC_23") (pintype "passive+no_connect"))
    )
    (net (code "59") (name "unconnected-(U4-NC-Pad24)") (class "Default")
      (node (ref "U4") (pin "24") (pinfunction "NC_24") (pintype "passive+no_connect"))
    )
    (net (code "60") (name "unconnected-(U4-SWCLK-Pad8)") (class "Default")
      (node (ref "U4") (pin "8") (pinfunction "SWCLK_8") (pintype "input+no_connect"))
    )
    (net (code "61") (name "unconnected-(U4-SWDIO-Pad7)") (class "Default")
      (node (ref "U4") (pin "7") (pinfunction "SWDIO_7") (pintype "bidirectional+no_connect"))
    )
    (net (code "62") (name "unconnected-(U4-XIN32-Pad27)") (class "Default")
      (node (ref "U4") (pin "27") (pinfunction "XIN32_27") (pintype "input+no_connect"))
    )
    (net (code "63") (name "unconnected-(U4-XOUT32-Pad26)") (class "Default")
      (node (ref "U4") (pin "26") (pinfunction "XOUT32_26") (pintype "passive+no_connect"))
    )
    (net (code "64") (name "unconnected-(U5C-PA0-Pad25)") (class "Default")
      (node (ref "U5") (pin "25") (pinfunction "PA0_25") (pintype "bidirectional+no_connect"))
    )
    (net (code "65") (name "unconnected-(U5C-PA1-Pad26)") (class "Default")
      (node (ref "U5") (pin "26") (pinfunction "PA1_26") (pintype "bidirectional+no_connect"))
    )
    (net (code "66") (name "unconnected-(U5C-PA4-Pad29)") (class "Default")
      (node (ref "U5") (pin "29") (pinfunction "PA4_29") (pintype "bidirectional"))
    )
    (net (code "67") (name "unconnected-(U5C-PD14-Pad23)") (class "Default")
      (node (ref "U5") (pin "23") (pinfunction "PD14_23") (pintype "bidirectional+no_connect"))
    )
    (net (code "68") (name "unconnected-(U5C-PD15-Pad24)") (class "Default")
      (node (ref "U5") (pin "24") (pinfunction "PD15_24") (pintype "bidirectional+no_connect"))
    )
    (net (code "69") (name "unconnected-(U6-LNA_EN-Pad13)") (class "Default")
      (node (ref "U6") (pin "13") (pinfunction "LNA_EN_13") (pintype "output+no_connect"))
    )
    (net (code "70") (name "unconnected-(U6-RESERVED-Pad15)") (class "Default")
      (node (ref "U6") (pin "15") (pinfunction "RESERVED_15") (pintype "tri_state+no_connect"))
    )
    (net (code "71") (name "unconnected-(U6-SAFEBOOT_N-Pad18)") (class "Default")
      (node (ref "U6") (pin "18") (pinfunction "SAFEBOOT_N_18") (pintype "input+no_connect"))
    )
    (net (code "72") (name "unconnected-(U6-SCL-Pad17)") (class "Default")
      (node (ref "U6") (pin "17") (pinfunction "SCL_17") (pintype "bidirectional+no_connect"))
    )
    (net (code "73") (name "unconnected-(U6-SDA-Pad16)") (class "Default")
      (node (ref "U6") (pin "16") (pinfunction "SDA_16") (pintype "bidirectional+no_connect"))
    )
    (net (code "74") (name "unconnected-(U6-VCC_RF-Pad14)") (class "Default")
      (node (ref "U6") (pin "14") (pinfunction "VCC_RF_14") (pintype "power_in+no_connect"))
    )
    (net (code "75") (name "unconnected-(U9-NC-Pad4)") (class "Default")
      (node (ref "U9") (pin "4") (pinfunction "NC_4") (pintype "passive+no_connect"))
    )
  )
)
